# haasoscope_pro_preinput_board.net
KiCad netlist of a schematic drawn in EAGLE
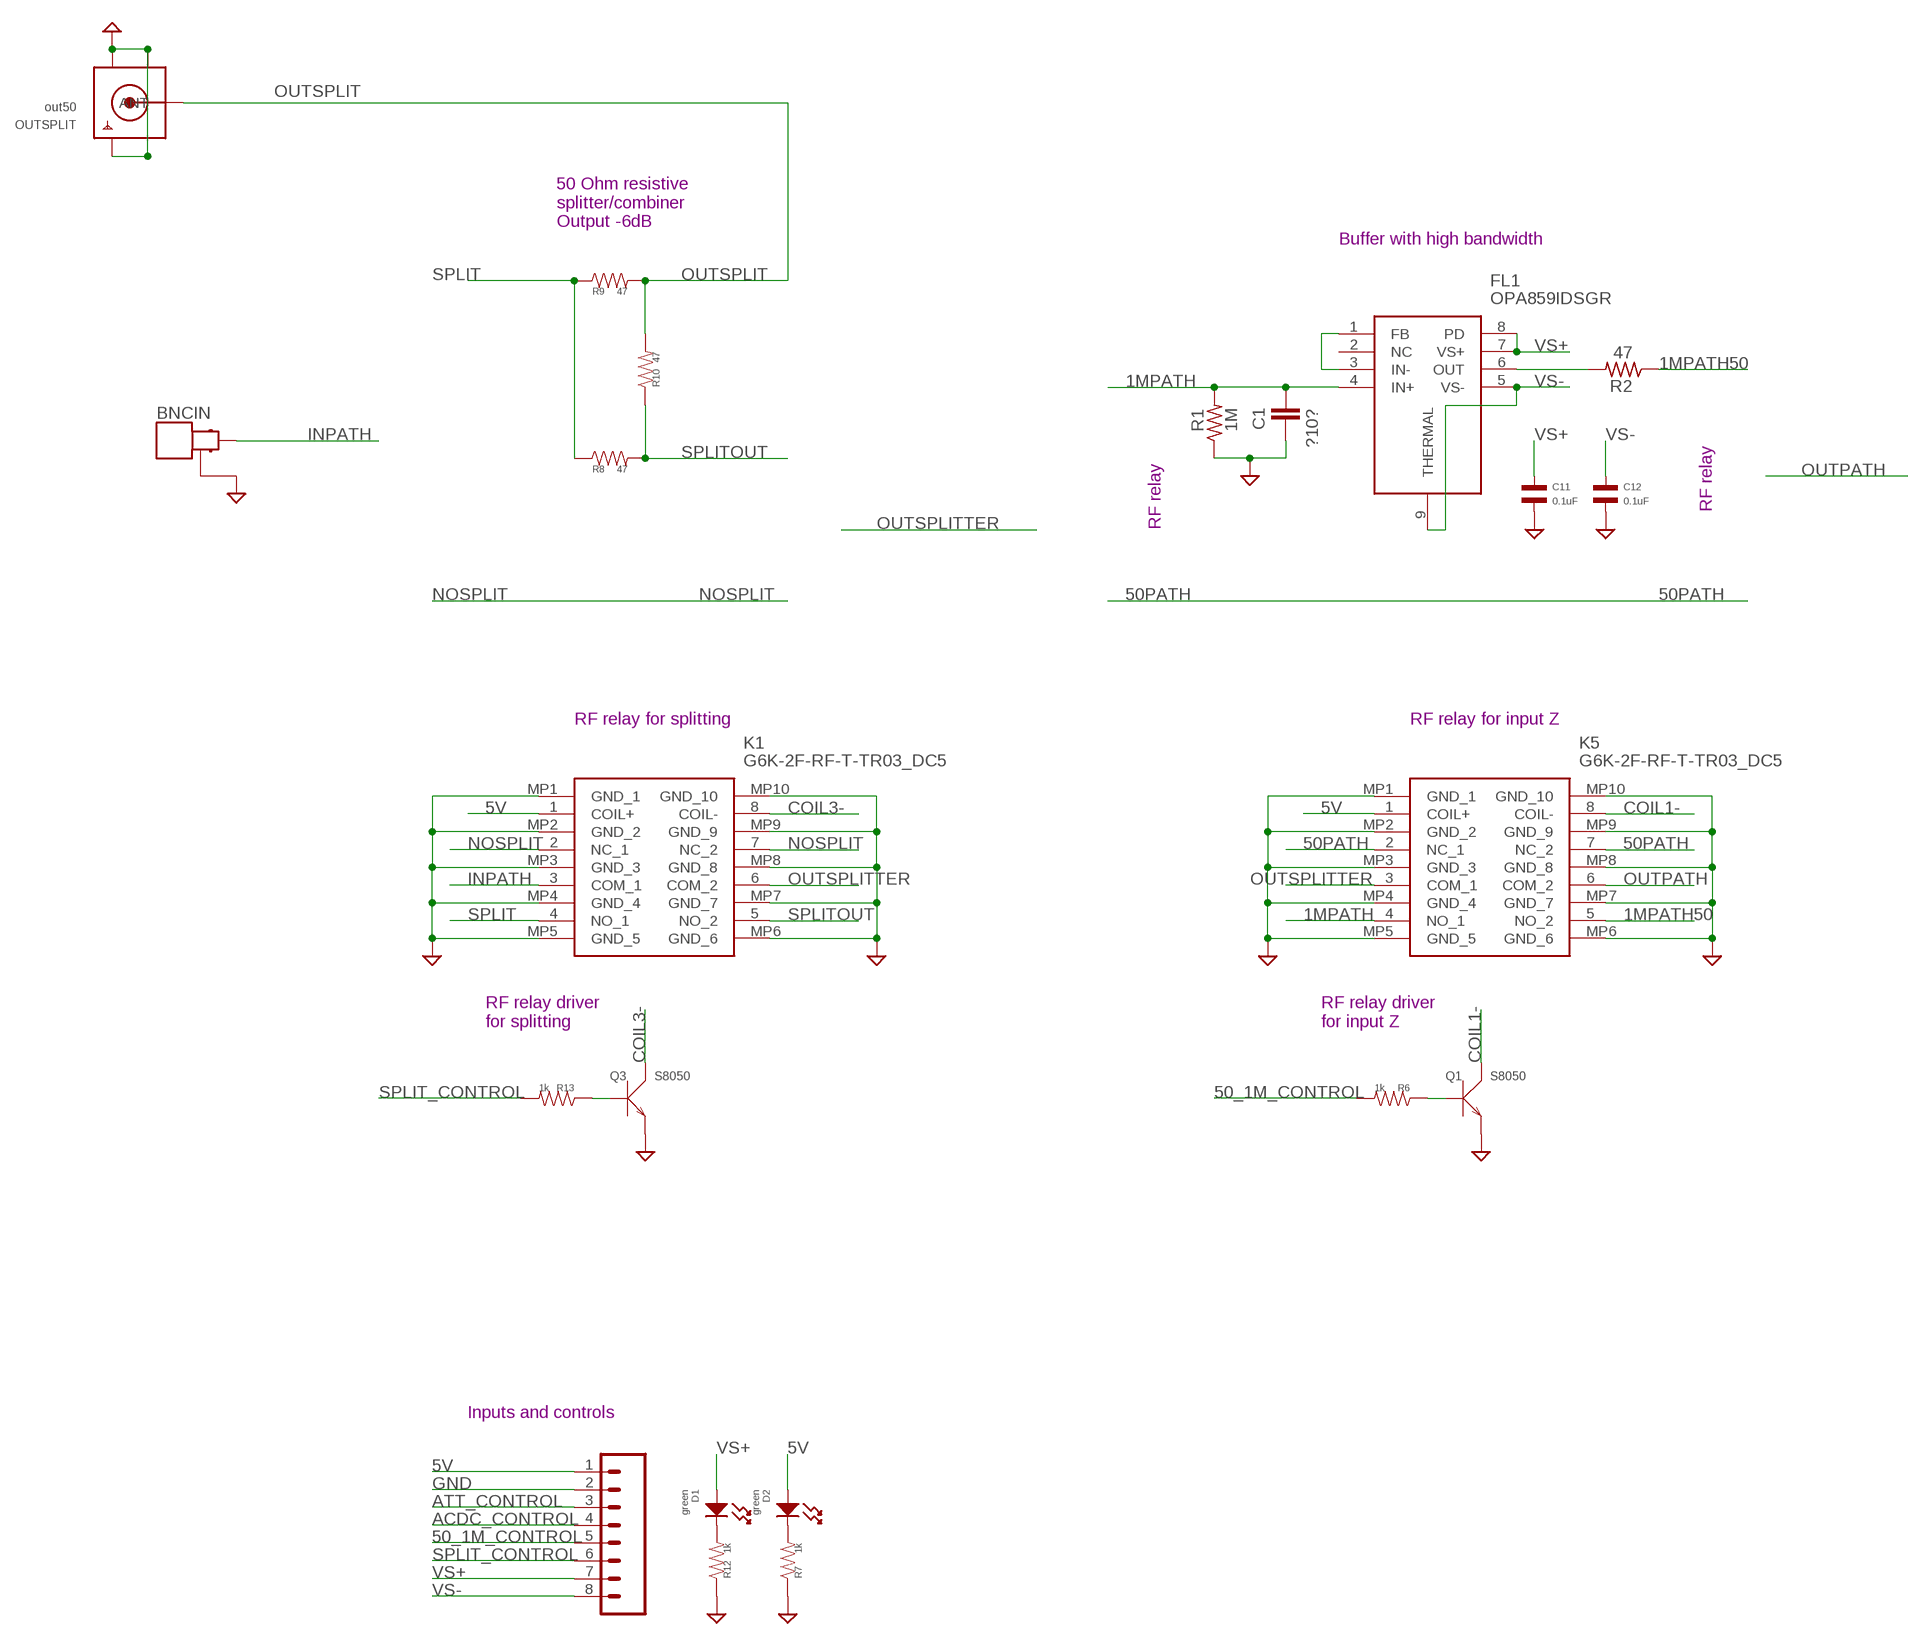
[diagram p0: schematic, sheet 1, part 1 of 2]
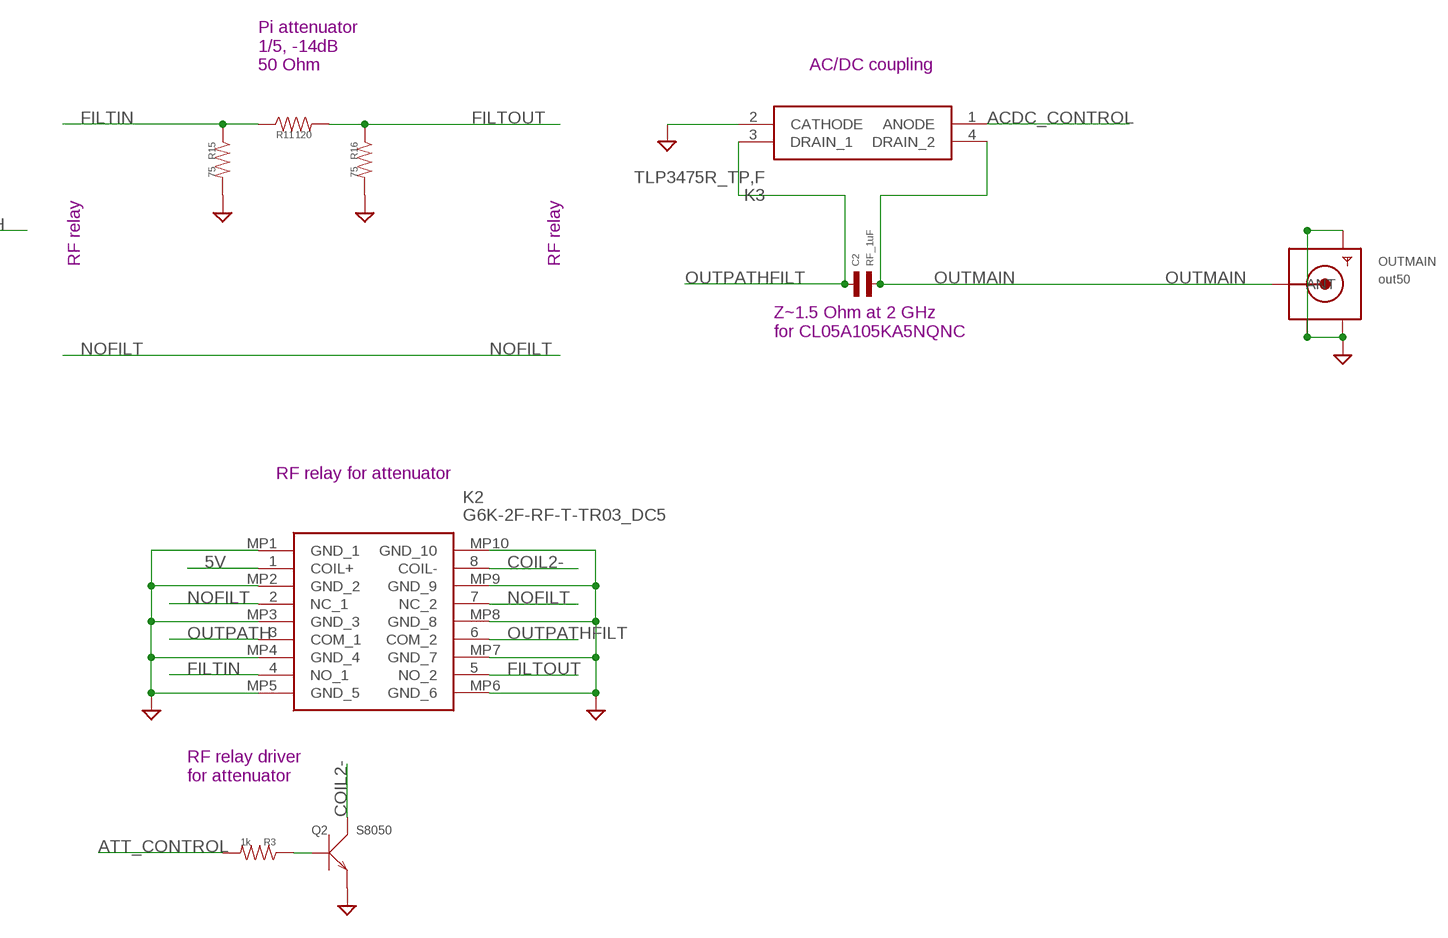
[diagram p1: schematic, sheet 1, part 2 of 2]

(export (version "E")
  (design (tool "Eeschema 10.0.6"))
  (components
    (comp (ref "BNCIN")
      (value "MOLEX_BNC_73100-0105")
      (footprint "eagle-import:MOLEX-BNC-73100-0105")
      (fields (field (name "MPN") "73100-0105"))
      (libsource (lib "eagle-import") (part "MOLEX_BNC_73100-0105"))
    )
    (comp (ref "C1")
      (value "?10?")
      (footprint "eagle-import:C0805")
      (libsource (lib "eagle-import") (part "C-EUC0805"))
    )
    (comp (ref "C2")
      (value "RF_1uF")
      (footprint "eagle-import:C0402")
      (libsource (lib "eagle-import") (part "CAPACITOR_NP_0402"))
    )
    (comp (ref "C11")
      (value "0.1uF")
      (footprint "eagle-import:C0402")
      (libsource (lib "eagle-import") (part "CAPACITOR_NP_0402"))
    )
    (comp (ref "C12")
      (value "0.1uF")
      (footprint "eagle-import:C0402")
      (libsource (lib "eagle-import") (part "CAPACITOR_NP_0402"))
    )
    (comp (ref "D1")
      (value "green")
      (footprint "eagle-import:LED0603")
      (fields (field (name "HOUSEPART") "NO"))
      (libsource (lib "eagle-import") (part "LED_SINGLE-0603"))
    )
    (comp (ref "D2")
      (value "green")
      (footprint "eagle-import:LED0603")
      (fields (field (name "HOUSEPART") "NO"))
      (libsource (lib "eagle-import") (part "LED_SINGLE-0603"))
    )
    (comp (ref "FL1")
      (value "OPA859IDSGR")
      (footprint "eagle-import:SON50P200X200X80-9N")
      (fields (field (name "MOUSER_PART_NUMBER") "595-OPA859IDSGR"))
      (libsource (lib "eagle-import") (part "OPA859IDSGR"))
    )
    (comp (ref "J4")
      (value "8pin")
      (footprint "eagle-import:1X08")
      (libsource (lib "eagle-import") (part "CONN_08{dblquote}"))
    )
    (comp (ref "K1")
      (value "G6K-2F-RF-T-TR03_DC5")
      (footprint "eagle-import:G6K2FRFTTR03DC5")
      (fields
        (field (name "MANUFACTURER_PART_NUMBER") "G6K-2F-RF-T-TR03 DC5")
        (field (name "MOUSER_PART_NUMBER") "653-G6K2FRFTTR03DC5")
      )
      (libsource (lib "eagle-import") (part "G6K-2F-RF-T-TR03_DC5"))
    )
    (comp (ref "K2")
      (value "G6K-2F-RF-T-TR03_DC5")
      (footprint "eagle-import:G6K2FRFTTR03DC5")
      (fields
        (field (name "MANUFACTURER_PART_NUMBER") "G6K-2F-RF-T-TR03 DC5")
        (field (name "MOUSER_PART_NUMBER") "653-G6K2FRFTTR03DC5")
      )
      (libsource (lib "eagle-import") (part "G6K-2F-RF-T-TR03_DC5"))
    )
    (comp (ref "K3")
      (value "TLP3475R_TP,F")
      (footprint "eagle-import:TLP3475RTPF")
      (fields
        (field (name "MANUFACTURER_PART_NUMBER") "TLP3475R(TP,F")
        (field (name "MOUSER_PART_NUMBER") "757-TLP3475RTPF")
        (field (name "MANUFACTURER_PART_NUMBER_1") "TLP3475R(TP,F")
      )
      (libsource (lib "eagle-import") (part "TLP3475R_TP,F"))
    )
    (comp (ref "K5")
      (value "G6K-2F-RF-T-TR03_DC5")
      (footprint "eagle-import:G6K2FRFTTR03DC5")
      (fields
        (field (name "MANUFACTURER_PART_NUMBER") "G6K-2F-RF-T-TR03 DC5")
        (field (name "MOUSER_PART_NUMBER") "653-G6K2FRFTTR03DC5")
      )
      (libsource (lib "eagle-import") (part "G6K-2F-RF-T-TR03_DC5"))
    )
    (comp (ref "OUTMAIN")
      (value "out50")
      (footprint "eagle-import:SMA_EDGELAUNCH")
      (libsource (lib "eagle-import") (part "SMACONNECTOR_EDGE"))
    )
    (comp (ref "OUTSPLIT")
      (value "out50")
      (footprint "eagle-import:SMA_EDGELAUNCH")
      (libsource (lib "eagle-import") (part "SMACONNECTOR_EDGE"))
    )
    (comp (ref "Q1")
      (value "S8050")
      (footprint "eagle-import:SOT-23")
      (libsource (lib "eagle-import") (part "SMD-TRANSISTORS-NPN-25V-500MW-S8050(SOT-23)"))
    )
    (comp (ref "Q2")
      (value "S8050")
      (footprint "eagle-import:SOT-23")
      (libsource (lib "eagle-import") (part "SMD-TRANSISTORS-NPN-25V-500MW-S8050(SOT-23)"))
    )
    (comp (ref "Q3")
      (value "S8050")
      (footprint "eagle-import:SOT-23")
      (libsource (lib "eagle-import") (part "SMD-TRANSISTORS-NPN-25V-500MW-S8050(SOT-23)"))
    )
    (comp (ref "R1")
      (value "1M")
      (footprint "eagle-import:R0805")
      (libsource (lib "eagle-import") (part "R-US_R0805"))
    )
    (comp (ref "R2")
      (value "47")
      (footprint "eagle-import:R0805")
      (libsource (lib "eagle-import") (part "R-US_R0805"))
    )
    (comp (ref "R3")
      (value "1k")
      (footprint "eagle-import:R0402")
      (libsource (lib "eagle-import") (part "RESISTOR_0402"))
    )
    (comp (ref "R6")
      (value "1k")
      (footprint "eagle-import:R0402")
      (libsource (lib "eagle-import") (part "RESISTOR_0402"))
    )
    (comp (ref "R7")
      (value "1k")
      (footprint "eagle-import:R0402")
      (libsource (lib "eagle-import") (part "RESISTOR_0402"))
    )
    (comp (ref "R8")
      (value "47")
      (footprint "eagle-import:R0402")
      (libsource (lib "eagle-import") (part "RESISTOR_0402"))
    )
    (comp (ref "R9")
      (value "47")
      (footprint "eagle-import:R0402")
      (libsource (lib "eagle-import") (part "RESISTOR_0402"))
    )
    (comp (ref "R10")
      (value "47")
      (footprint "eagle-import:R0402")
      (libsource (lib "eagle-import") (part "RESISTOR_0402"))
    )
    (comp (ref "R11")
      (value "120")
      (footprint "eagle-import:R0402")
      (libsource (lib "eagle-import") (part "RESISTOR_0402"))
    )
    (comp (ref "R12")
      (value "1k")
      (footprint "eagle-import:R0402")
      (libsource (lib "eagle-import") (part "RESISTOR_0402"))
    )
    (comp (ref "R13")
      (value "1k")
      (footprint "eagle-import:R0402")
      (libsource (lib "eagle-import") (part "RESISTOR_0402"))
    )
    (comp (ref "R15")
      (value "75")
      (footprint "eagle-import:R0402")
      (libsource (lib "eagle-import") (part "RESISTOR_0402"))
    )
    (comp (ref "R16")
      (value "75")
      (footprint "eagle-import:R0402")
      (libsource (lib "eagle-import") (part "RESISTOR_0402"))
    )
  )
  (nets
    (net (code "1") (name "/1MPATH") (class "Default")
      (node (ref "C1") (pin "2") (pinfunction "2_2") (pintype "passive"))
      (node (ref "FL1") (pin "4") (pinfunction "IN+_4") (pintype "input"))
      (node (ref "K5") (pin "4") (pinfunction "NO_1_4") (pintype "bidirectional"))
      (node (ref "R1") (pin "2") (pinfunction "2_2") (pintype "passive"))
    )
    (net (code "2") (name "/1MPATH50") (class "Default")
      (node (ref "K5") (pin "5") (pinfunction "NO_2_5") (pintype "bidirectional"))
      (node (ref "R2") (pin "1") (pinfunction "1_1") (pintype "passive"))
    )
    (net (code "3") (name "/5V") (class "Default")
      (node (ref "D2") (pin "ANODE") (pinfunction "ANODE_ANODE") (pintype "power_in"))
      (node (ref "J4") (pin "1") (pinfunction "1_1") (pintype "passive"))
      (node (ref "K1") (pin "1") (pinfunction "COIL+_1") (pintype "bidirectional"))
      (node (ref "K2") (pin "1") (pinfunction "COIL+_1") (pintype "bidirectional"))
      (node (ref "K5") (pin "1") (pinfunction "COIL+_1") (pintype "bidirectional"))
    )
    (net (code "4") (name "/50PATH") (class "Default")
      (node (ref "K5") (pin "2") (pinfunction "NC_1_2") (pintype "bidirectional"))
      (node (ref "K5") (pin "7") (pinfunction "NC_2_7") (pintype "bidirectional"))
    )
    (net (code "5") (name "/50_1M_CONTROL") (class "Default")
      (node (ref "J4") (pin "5") (pinfunction "5_5") (pintype "passive"))
      (node (ref "R6") (pin "P$2") (pinfunction "P$2_P$2") (pintype "passive"))
    )
    (net (code "6") (name "/ACDC_CONTROL") (class "Default")
      (node (ref "J4") (pin "4") (pinfunction "4_4") (pintype "passive"))
      (node (ref "K3") (pin "1") (pinfunction "ANODE_1") (pintype "bidirectional"))
    )
    (net (code "7") (name "/ATT_CONTROL") (class "Default")
      (node (ref "J4") (pin "3") (pinfunction "3_3") (pintype "passive"))
      (node (ref "R3") (pin "P$2") (pinfunction "P$2_P$2") (pintype "passive"))
    )
    (net (code "8") (name "/COIL1-") (class "Default")
      (node (ref "K5") (pin "8") (pinfunction "COIL-_8") (pintype "bidirectional"))
      (node (ref "Q1") (pin "3") (pinfunction "C_3") (pintype "passive"))
    )
    (net (code "9") (name "/COIL2-") (class "Default")
      (node (ref "K2") (pin "8") (pinfunction "COIL-_8") (pintype "bidirectional"))
      (node (ref "Q2") (pin "3") (pinfunction "C_3") (pintype "passive"))
    )
    (net (code "10") (name "/COIL3-") (class "Default")
      (node (ref "K1") (pin "8") (pinfunction "COIL-_8") (pintype "bidirectional"))
      (node (ref "Q3") (pin "3") (pinfunction "C_3") (pintype "passive"))
    )
    (net (code "11") (name "/FILTIN") (class "Default")
      (node (ref "K2") (pin "4") (pinfunction "NO_1_4") (pintype "bidirectional"))
      (node (ref "R11") (pin "P$1") (pinfunction "P$1_P$1") (pintype "passive"))
      (node (ref "R15") (pin "P$1") (pinfunction "P$1_P$1") (pintype "passive"))
    )
    (net (code "12") (name "/FILTOUT") (class "Default")
      (node (ref "K2") (pin "5") (pinfunction "NO_2_5") (pintype "bidirectional"))
      (node (ref "R11") (pin "P$2") (pinfunction "P$2_P$2") (pintype "passive"))
      (node (ref "R16") (pin "P$1") (pinfunction "P$1_P$1") (pintype "passive"))
    )
    (net (code "13") (name "/INPATH") (class "Default")
      (node (ref "BNCIN") (pin "SIGNAL") (pinfunction "SIGNAL_SIGNAL") (pintype "bidirectional"))
      (node (ref "K1") (pin "3") (pinfunction "COM_1_3") (pintype "bidirectional"))
    )
    (net (code "14") (name "/NOFILT") (class "Default")
      (node (ref "K2") (pin "2") (pinfunction "NC_1_2") (pintype "bidirectional"))
      (node (ref "K2") (pin "7") (pinfunction "NC_2_7") (pintype "bidirectional"))
    )
    (net (code "15") (name "/NOSPLIT") (class "Default")
      (node (ref "K1") (pin "2") (pinfunction "NC_1_2") (pintype "bidirectional"))
      (node (ref "K1") (pin "7") (pinfunction "NC_2_7") (pintype "bidirectional"))
    )
    (net (code "16") (name "/OUTMAIN") (class "Default")
      (node (ref "C2") (pin "P$2") (pinfunction "P$2_P$2") (pintype "passive"))
      (node (ref "K3") (pin "4") (pinfunction "DRAIN_2_4") (pintype "bidirectional"))
      (node (ref "OUTMAIN") (pin "P") (pinfunction "ANT_P") (pintype "bidirectional"))
    )
    (net (code "17") (name "/OUTPATH") (class "Default")
      (node (ref "K2") (pin "3") (pinfunction "COM_1_3") (pintype "bidirectional"))
      (node (ref "K5") (pin "6") (pinfunction "COM_2_6") (pintype "bidirectional"))
    )
    (net (code "18") (name "/OUTPATHFILT") (class "Default")
      (node (ref "C2") (pin "P$1") (pinfunction "P$1_P$1") (pintype "passive"))
      (node (ref "K2") (pin "6") (pinfunction "COM_2_6") (pintype "bidirectional"))
      (node (ref "K3") (pin "3") (pinfunction "DRAIN_1_3") (pintype "bidirectional"))
    )
    (net (code "19") (name "/OUTSPLIT") (class "Default")
      (node (ref "OUTSPLIT") (pin "P") (pinfunction "ANT_P") (pintype "bidirectional"))
      (node (ref "R10") (pin "P$2") (pinfunction "P$2_P$2") (pintype "passive"))
      (node (ref "R9") (pin "P$2") (pinfunction "P$2_P$2") (pintype "passive"))
    )
    (net (code "20") (name "/OUTSPLITTER") (class "Default")
      (node (ref "K1") (pin "6") (pinfunction "COM_2_6") (pintype "bidirectional"))
      (node (ref "K5") (pin "3") (pinfunction "COM_1_3") (pintype "bidirectional"))
    )
    (net (code "21") (name "/SPLIT") (class "Default")
      (node (ref "K1") (pin "4") (pinfunction "NO_1_4") (pintype "bidirectional"))
      (node (ref "R8") (pin "P$1") (pinfunction "P$1_P$1") (pintype "passive"))
      (node (ref "R9") (pin "P$1") (pinfunction "P$1_P$1") (pintype "passive"))
    )
    (net (code "22") (name "/SPLITOUT") (class "Default")
      (node (ref "K1") (pin "5") (pinfunction "NO_2_5") (pintype "bidirectional"))
      (node (ref "R10") (pin "P$1") (pinfunction "P$1_P$1") (pintype "passive"))
      (node (ref "R8") (pin "P$2") (pinfunction "P$2_P$2") (pintype "passive"))
    )
    (net (code "23") (name "/SPLIT_CONTROL") (class "Default")
      (node (ref "J4") (pin "6") (pinfunction "6_6") (pintype "passive"))
      (node (ref "R13") (pin "P$2") (pinfunction "P$2_P$2") (pintype "passive"))
    )
    (net (code "24") (name "/VS+") (class "Default")
      (node (ref "C11") (pin "P$1") (pinfunction "P$1_P$1") (pintype "passive"))
      (node (ref "D1") (pin "ANODE") (pinfunction "ANODE_ANODE") (pintype "power_in"))
      (node (ref "FL1") (pin "7") (pinfunction "VS+_7") (pintype "power_in"))
      (node (ref "FL1") (pin "8") (pinfunction "PD_8") (pintype "input"))
      (node (ref "J4") (pin "7") (pinfunction "7_7") (pintype "passive"))
    )
    (net (code "25") (name "/VS-") (class "Default")
      (node (ref "C12") (pin "P$1") (pinfunction "P$1_P$1") (pintype "passive"))
      (node (ref "FL1") (pin "5") (pinfunction "VS-_5") (pintype "power_in"))
      (node (ref "FL1") (pin "9") (pinfunction "THERMAL_9") (pintype "bidirectional"))
      (node (ref "J4") (pin "8") (pinfunction "8_8") (pintype "passive"))
    )
    (net (code "26") (name "GND") (class "Default")
      (node (ref "BNCIN") (pin "GND1") (pinfunction "GND_GND1") (pintype "bidirectional"))
      (node (ref "BNCIN") (pin "GND2") (pinfunction "GND_GND2") (pintype "bidirectional"))
      (node (ref "C1") (pin "1") (pinfunction "1_1") (pintype "passive"))
      (node (ref "C11") (pin "P$2") (pinfunction "P$2_P$2") (pintype "passive"))
      (node (ref "C12") (pin "P$2") (pinfunction "P$2_P$2") (pintype "passive"))
      (node (ref "J4") (pin "2") (pinfunction "2_2") (pintype "passive"))
      (node (ref "K1") (pin "MP1") (pinfunction "GND_1_MP1") (pintype "bidirectional"))
      (node (ref "K1") (pin "MP10") (pinfunction "GND_10_MP10") (pintype "bidirectional"))
      (node (ref "K1") (pin "MP2") (pinfunction "GND_2_MP2") (pintype "bidirectional"))
      (node (ref "K1") (pin "MP3") (pinfunction "GND_3_MP3") (pintype "bidirectional"))
      (node (ref "K1") (pin "MP4") (pinfunction "GND_4_MP4") (pintype "bidirectional"))
      (node (ref "K1") (pin "MP5") (pinfunction "GND_5_MP5") (pintype "bidirectional"))
      (node (ref "K1") (pin "MP6") (pinfunction "GND_6_MP6") (pintype "bidirectional"))
      (node (ref "K1") (pin "MP7") (pinfunction "GND_7_MP7") (pintype "bidirectional"))
      (node (ref "K1") (pin "MP8") (pinfunction "GND_8_MP8") (pintype "bidirectional"))
      (node (ref "K1") (pin "MP9") (pinfunction "GND_9_MP9") (pintype "bidirectional"))
      (node (ref "K2") (pin "MP1") (pinfunction "GND_1_MP1") (pintype "bidirectional"))
      (node (ref "K2") (pin "MP10") (pinfunction "GND_10_MP10") (pintype "bidirectional"))
      (node (ref "K2") (pin "MP2") (pinfunction "GND_2_MP2") (pintype "bidirectional"))
      (node (ref "K2") (pin "MP3") (pinfunction "GND_3_MP3") (pintype "bidirectional"))
      (node (ref "K2") (pin "MP4") (pinfunction "GND_4_MP4") (pintype "bidirectional"))
      (node (ref "K2") (pin "MP5") (pinfunction "GND_5_MP5") (pintype "bidirectional"))
      (node (ref "K2") (pin "MP6") (pinfunction "GND_6_MP6") (pintype "bidirectional"))
      (node (ref "K2") (pin "MP7") (pinfunction "GND_7_MP7") (pintype "bidirectional"))
      (node (ref "K2") (pin "MP8") (pinfunction "GND_8_MP8") (pintype "bidirectional"))
      (node (ref "K2") (pin "MP9") (pinfunction "GND_9_MP9") (pintype "bidirectional"))
      (node (ref "K3") (pin "2") (pinfunction "CATHODE_2") (pintype "bidirectional"))
      (node (ref "K5") (pin "MP1") (pinfunction "GND_1_MP1") (pintype "bidirectional"))
      (node (ref "K5") (pin "MP10") (pinfunction "GND_10_MP10") (pintype "bidirectional"))
      (node (ref "K5") (pin "MP2") (pinfunction "GND_2_MP2") (pintype "bidirectional"))
      (node (ref "K5") (pin "MP3") (pinfunction "GND_3_MP3") (pintype "bidirectional"))
      (node (ref "K5") (pin "MP4") (pinfunction "GND_4_MP4") (pintype "bidirectional"))
      (node (ref "K5") (pin "MP5") (pinfunction "GND_5_MP5") (pintype "bidirectional"))
      (node (ref "K5") (pin "MP6") (pinfunction "GND_6_MP6") (pintype "bidirectional"))
      (node (ref "K5") (pin "MP7") (pinfunction "GND_7_MP7") (pintype "bidirectional"))
      (node (ref "K5") (pin "MP8") (pinfunction "GND_8_MP8") (pintype "bidirectional"))
      (node (ref "K5") (pin "MP9") (pinfunction "GND_9_MP9") (pintype "bidirectional"))
      (node (ref "OUTMAIN") (pin "GND@1") (pinfunction "GND4_GND@1") (pintype "power_in"))
      (node (ref "OUTMAIN") (pin "GND@2") (pinfunction "GND3_GND@2") (pintype "power_in"))
      (node (ref "OUTMAIN") (pin "GND@3") (pinfunction "GND2_GND@3") (pintype "power_in"))
      (node (ref "OUTMAIN") (pin "GND@4") (pinfunction "GND1_GND@4") (pintype "power_in"))
      (node (ref "OUTSPLIT") (pin "GND@1") (pinfunction "GND4_GND@1") (pintype "power_in"))
      (node (ref "OUTSPLIT") (pin "GND@2") (pinfunction "GND3_GND@2") (pintype "power_in"))
      (node (ref "OUTSPLIT") (pin "GND@3") (pinfunction "GND2_GND@3") (pintype "power_in"))
      (node (ref "OUTSPLIT") (pin "GND@4") (pinfunction "GND1_GND@4") (pintype "power_in"))
      (node (ref "Q1") (pin "2") (pinfunction "E_2") (pintype "passive"))
      (node (ref "Q2") (pin "2") (pinfunction "E_2") (pintype "passive"))
      (node (ref "Q3") (pin "2") (pinfunction "E_2") (pintype "passive"))
      (node (ref "R1") (pin "1") (pinfunction "1_1") (pintype "passive"))
      (node (ref "R12") (pin "P$1") (pinfunction "P$1_P$1") (pintype "passive"))
      (node (ref "R15") (pin "P$2") (pinfunction "P$2_P$2") (pintype "passive"))
      (node (ref "R16") (pin "P$2") (pinfunction "P$2_P$2") (pintype "passive"))
      (node (ref "R7") (pin "P$1") (pinfunction "P$1_P$1") (pintype "passive"))
    )
    (net (code "27") (name "Net-(D1-PadCATHODE)") (class "Default")
      (node (ref "D1") (pin "CATHODE") (pinfunction "CATHODE_CATHODE") (pintype "power_in"))
      (node (ref "R12") (pin "P$2") (pinfunction "P$2_P$2") (pintype "passive"))
    )
    (net (code "28") (name "Net-(D2-PadCATHODE)") (class "Default")
      (node (ref "D2") (pin "CATHODE") (pinfunction "CATHODE_CATHODE") (pintype "power_in"))
      (node (ref "R7") (pin "P$2") (pinfunction "P$2_P$2") (pintype "passive"))
    )
    (net (code "29") (name "Net-(FL1-FB)") (class "Default")
      (node (ref "FL1") (pin "1") (pinfunction "FB_1") (pintype "input"))
      (node (ref "FL1") (pin "3") (pinfunction "IN-_3") (pintype "input"))
    )
    (net (code "30") (name "Net-(FL1-OUT)") (class "Default")
      (node (ref "FL1") (pin "6") (pinfunction "OUT_6") (pintype "output"))
      (node (ref "R2") (pin "2") (pinfunction "2_2") (pintype "passive"))
    )
    (net (code "31") (name "Net-(Q1-B)") (class "Default")
      (node (ref "Q1") (pin "1") (pinfunction "B_1") (pintype "passive"))
      (node (ref "R6") (pin "P$1") (pinfunction "P$1_P$1") (pintype "passive"))
    )
    (net (code "32") (name "Net-(Q2-B)") (class "Default")
      (node (ref "Q2") (pin "1") (pinfunction "B_1") (pintype "passive"))
      (node (ref "R3") (pin "P$1") (pinfunction "P$1_P$1") (pintype "passive"))
    )
    (net (code "33") (name "Net-(Q3-B)") (class "Default")
      (node (ref "Q3") (pin "1") (pinfunction "B_1") (pintype "passive"))
      (node (ref "R13") (pin "P$1") (pinfunction "P$1_P$1") (pintype "passive"))
    )
    (net (code "34") (name "unconnected-(FL1-NC-Pad2)") (class "Default")
      (node (ref "FL1") (pin "2") (pinfunction "NC_2") (pintype "no_connect"))
    )
  )
)
